# SCH_7Seg.net
KiCad netlist of a schematic drawn in Altium Designer
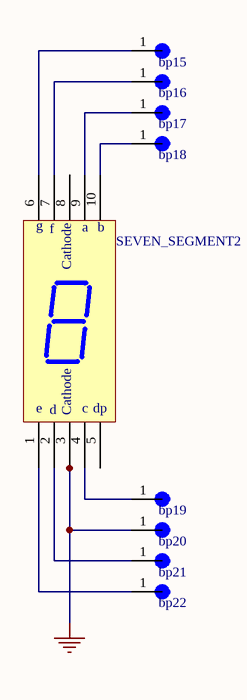
[diagram p0: SCH_7Seg.SchDoc]

(export (version "E")
  (design (tool "Eeschema 10.0.6"))
  (components
    (comp (ref "bp15")
      (value "Battery Pad")
      (footprint "Battery pad")
      (libsource (lib "Schlib1") (part "Battery Pad"))
    )
    (comp (ref "bp16")
      (value "Battery Pad")
      (footprint "Battery pad")
      (libsource (lib "Schlib1") (part "Battery Pad"))
    )
    (comp (ref "bp17")
      (value "Battery Pad")
      (footprint "Battery pad")
      (libsource (lib "Schlib1") (part "Battery Pad"))
    )
    (comp (ref "bp18")
      (value "Battery Pad")
      (footprint "Battery pad")
      (libsource (lib "Schlib1") (part "Battery Pad"))
    )
    (comp (ref "bp19")
      (value "Battery Pad")
      (footprint "Battery pad")
      (libsource (lib "Schlib1") (part "Battery Pad"))
    )
    (comp (ref "bp20")
      (value "Battery Pad")
      (footprint "Battery pad")
      (libsource (lib "Schlib1") (part "Battery Pad"))
    )
    (comp (ref "bp21")
      (value "Battery Pad")
      (footprint "Battery pad")
      (libsource (lib "Schlib1") (part "Battery Pad"))
    )
    (comp (ref "bp22")
      (value "Battery Pad")
      (footprint "Battery pad")
      (libsource (lib "Schlib1") (part "Battery Pad"))
    )
    (comp (ref "SEVEN_SEGMENT2")
      (value "CC_SEVEN_SEGMENT")
      (footprint "7SEG-Avago-Broadcam_HDSP-5551_0")
      (libsource (lib "Schlib1") (part "CC_SEVEN_SEGMENT"))
    )
  )
  (nets
    (net (code "1") (name "GND") (class "Default")
      (node (ref "SEVEN_SEGMENT2") (pin "3") (pinfunction "3_3") (pintype "passive"))
      (node (ref "SEVEN_SEGMENT2") (pin "8") (pinfunction "8_8") (pintype "passive"))
      (node (ref "bp20") (pin "1") (pinfunction "1_1") (pintype "passive"))
    )
    (net (code "2") (name "Net-(SEVEN_SEGMENT2-Pad1)") (class "Default")
      (node (ref "SEVEN_SEGMENT2") (pin "1") (pinfunction "1_1") (pintype "passive"))
      (node (ref "bp22") (pin "1") (pinfunction "1_1") (pintype "passive"))
    )
    (net (code "3") (name "Net-(SEVEN_SEGMENT2-Pad2)") (class "Default")
      (node (ref "SEVEN_SEGMENT2") (pin "2") (pinfunction "2_2") (pintype "passive"))
      (node (ref "bp21") (pin "1") (pinfunction "1_1") (pintype "passive"))
    )
    (net (code "4") (name "Net-(SEVEN_SEGMENT2-Pad4)") (class "Default")
      (node (ref "SEVEN_SEGMENT2") (pin "4") (pinfunction "4_4") (pintype "passive"))
      (node (ref "bp19") (pin "1") (pinfunction "1_1") (pintype "passive"))
    )
    (net (code "5") (name "Net-(SEVEN_SEGMENT2-Pad6)") (class "Default")
      (node (ref "SEVEN_SEGMENT2") (pin "6") (pinfunction "6_6") (pintype "passive"))
      (node (ref "bp15") (pin "1") (pinfunction "1_1") (pintype "passive"))
    )
    (net (code "6") (name "Net-(SEVEN_SEGMENT2-Pad7)") (class "Default")
      (node (ref "SEVEN_SEGMENT2") (pin "7") (pinfunction "7_7") (pintype "passive"))
      (node (ref "bp16") (pin "1") (pinfunction "1_1") (pintype "passive"))
    )
    (net (code "7") (name "Net-(SEVEN_SEGMENT2-Pad9)") (class "Default")
      (node (ref "SEVEN_SEGMENT2") (pin "9") (pinfunction "9_9") (pintype "passive"))
      (node (ref "bp17") (pin "1") (pinfunction "1_1") (pintype "passive"))
    )
    (net (code "8") (name "Net-(SEVEN_SEGMENT2-Pad10)") (class "Default")
      (node (ref "SEVEN_SEGMENT2") (pin "10") (pinfunction "10_10") (pintype "passive"))
      (node (ref "bp18") (pin "1") (pinfunction "1_1") (pintype "passive"))
    )
    (net (code "9") (name "unconnected-(SEVEN_SEGMENT2-Pad5)") (class "Default")
      (node (ref "SEVEN_SEGMENT2") (pin "5") (pinfunction "5_5") (pintype "passive"))
    )
  )
)
